# RS485_to_Neopixel.net
KiCad netlist of a schematic drawn in EAGLE
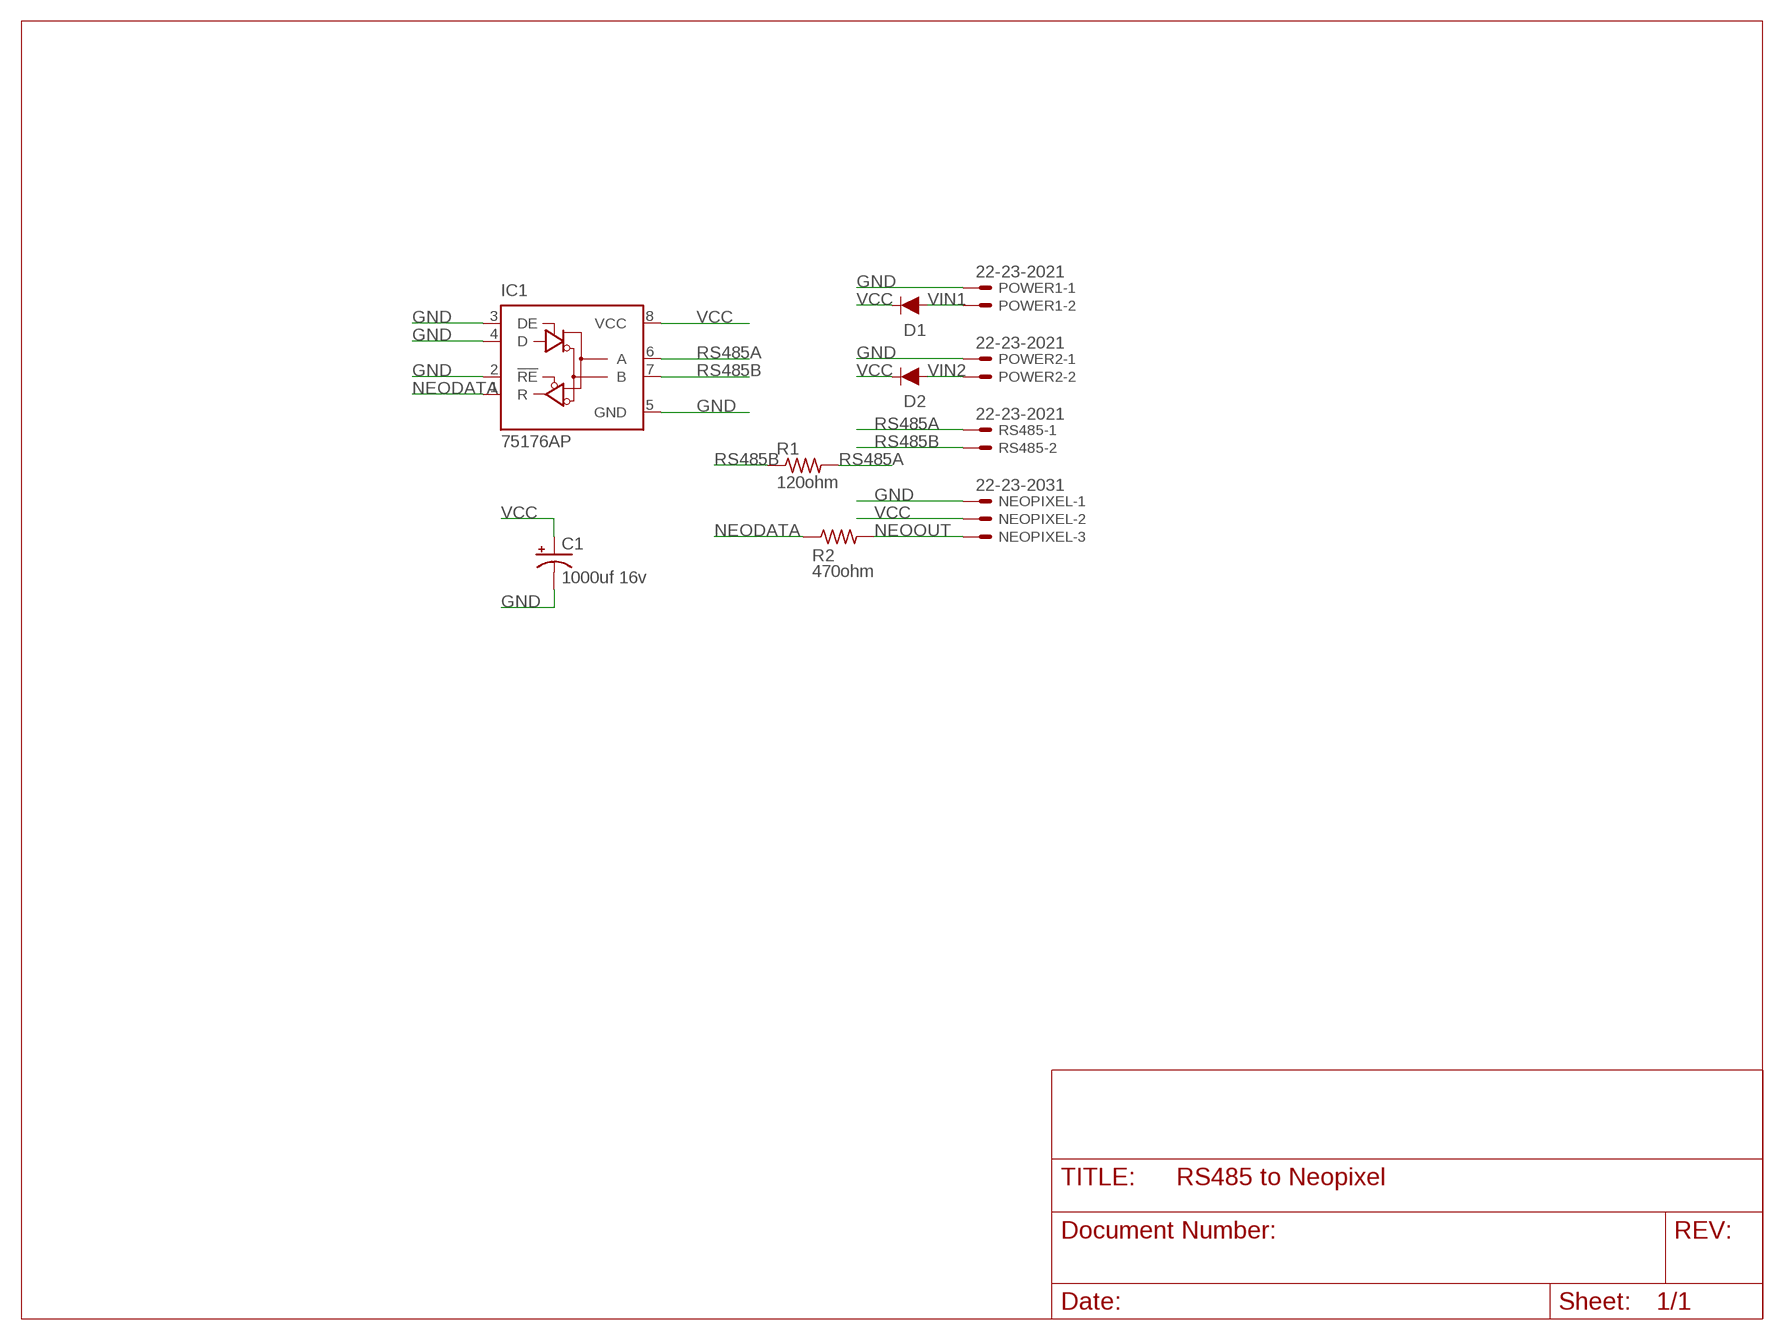
[diagram p0: schematic, sheet 1]

(export (version "E")
  (design (tool "Eeschema 10.0.6"))
  (components
    (comp (ref "C1")
      (value "1000uf 16v")
      (footprint "eagle-import:CPOL-RADIAL-5MM-10MM")
      (libsource (lib "eagle-import") (part "1000UF-RADIAL-5MM-25V-20%"))
    )
    (comp (ref "D1")
      (value "1A/50V/1.1V")
      (footprint "eagle-import:DIODE-1N4001")
      (libsource (lib "eagle-import") (part "DIODE-PTH"))
    )
    (comp (ref "D2")
      (value "1A/50V/1.1V")
      (footprint "eagle-import:DIODE-1N4001")
      (libsource (lib "eagle-import") (part "DIODE-PTH"))
    )
    (comp (ref "IC1")
      (value "75176AP")
      (footprint "eagle-import:DIL08")
      (libsource (lib "eagle-import") (part "75176AP"))
    )
    (comp (ref "NEOPIXEL")
      (value "22-23-2031")
      (footprint "eagle-import:22-23-2031")
      (fields (field (name "MF") "MOLEX"))
      (libsource (lib "eagle-import") (part "22-23-2031"))
    )
    (comp (ref "POWER1")
      (value "22-23-2021")
      (footprint "eagle-import:22-23-2021")
      (fields (field (name "MF") "MOLEX"))
      (libsource (lib "eagle-import") (part "22-23-2021"))
    )
    (comp (ref "POWER2")
      (value "22-23-2021")
      (footprint "eagle-import:22-23-2021")
      (fields (field (name "MF") "MOLEX"))
      (libsource (lib "eagle-import") (part "22-23-2021"))
    )
    (comp (ref "R1")
      (value "120ohm")
      (footprint "eagle-import:0207_10")
      (libsource (lib "eagle-import") (part "R-US_0207/10"))
    )
    (comp (ref "R2")
      (value "470ohm")
      (footprint "eagle-import:0207_10")
      (libsource (lib "eagle-import") (part "R-US_0207/10"))
    )
    (comp (ref "RS485")
      (value "22-23-2021")
      (footprint "eagle-import:22-23-2021")
      (fields (field (name "MF") "MOLEX"))
      (libsource (lib "eagle-import") (part "22-23-2021"))
    )
  )
  (nets
    (net (code "1") (name "/GND") (class "Default")
      (node (ref "C1") (pin "-") (pinfunction "-_-") (pintype "passive"))
      (node (ref "IC1") (pin "2") (pinfunction "~{RE}_2") (pintype "input"))
      (node (ref "IC1") (pin "3") (pinfunction "DE_3") (pintype "input"))
      (node (ref "IC1") (pin "4") (pinfunction "D_4") (pintype "input"))
      (node (ref "IC1") (pin "5") (pinfunction "GND_5") (pintype "power_in"))
      (node (ref "NEOPIXEL") (pin "1") (pinfunction "S_1") (pintype "passive"))
      (node (ref "POWER1") (pin "1") (pinfunction "S_1") (pintype "passive"))
      (node (ref "POWER2") (pin "1") (pinfunction "S_1") (pintype "passive"))
    )
    (net (code "2") (name "/NEODATA") (class "Default")
      (node (ref "IC1") (pin "1") (pinfunction "R_1") (pintype "input"))
      (node (ref "R2") (pin "1") (pinfunction "1_1") (pintype "passive"))
    )
    (net (code "3") (name "/NEOOUT") (class "Default")
      (node (ref "NEOPIXEL") (pin "3") (pinfunction "S_3") (pintype "passive"))
      (node (ref "R2") (pin "2") (pinfunction "2_2") (pintype "passive"))
    )
    (net (code "4") (name "/RS485A") (class "Default")
      (node (ref "IC1") (pin "6") (pinfunction "A_6") (pintype "output"))
      (node (ref "R1") (pin "2") (pinfunction "2_2") (pintype "passive"))
      (node (ref "RS485") (pin "1") (pinfunction "S_1") (pintype "passive"))
    )
    (net (code "5") (name "/RS485B") (class "Default")
      (node (ref "IC1") (pin "7") (pinfunction "B_7") (pintype "output"))
      (node (ref "R1") (pin "1") (pinfunction "1_1") (pintype "passive"))
      (node (ref "RS485") (pin "2") (pinfunction "S_2") (pintype "passive"))
    )
    (net (code "6") (name "/VCC") (class "Default")
      (node (ref "C1") (pin "+") (pinfunction "+_+") (pintype "passive"))
      (node (ref "D1") (pin "C") (pinfunction "C_C") (pintype "passive"))
      (node (ref "D2") (pin "C") (pinfunction "C_C") (pintype "passive"))
      (node (ref "IC1") (pin "8") (pinfunction "VCC_8") (pintype "power_in"))
      (node (ref "NEOPIXEL") (pin "2") (pinfunction "S_2") (pintype "passive"))
    )
    (net (code "7") (name "/VIN1") (class "Default")
      (node (ref "D1") (pin "A") (pinfunction "A_A") (pintype "passive"))
      (node (ref "POWER1") (pin "2") (pinfunction "S_2") (pintype "passive"))
    )
    (net (code "8") (name "/VIN2") (class "Default")
      (node (ref "D2") (pin "A") (pinfunction "A_A") (pintype "passive"))
      (node (ref "POWER2") (pin "2") (pinfunction "S_2") (pintype "passive"))
    )
  )
)
